# Tree.net
KiCad netlist of a schematic drawn in Altium Designer
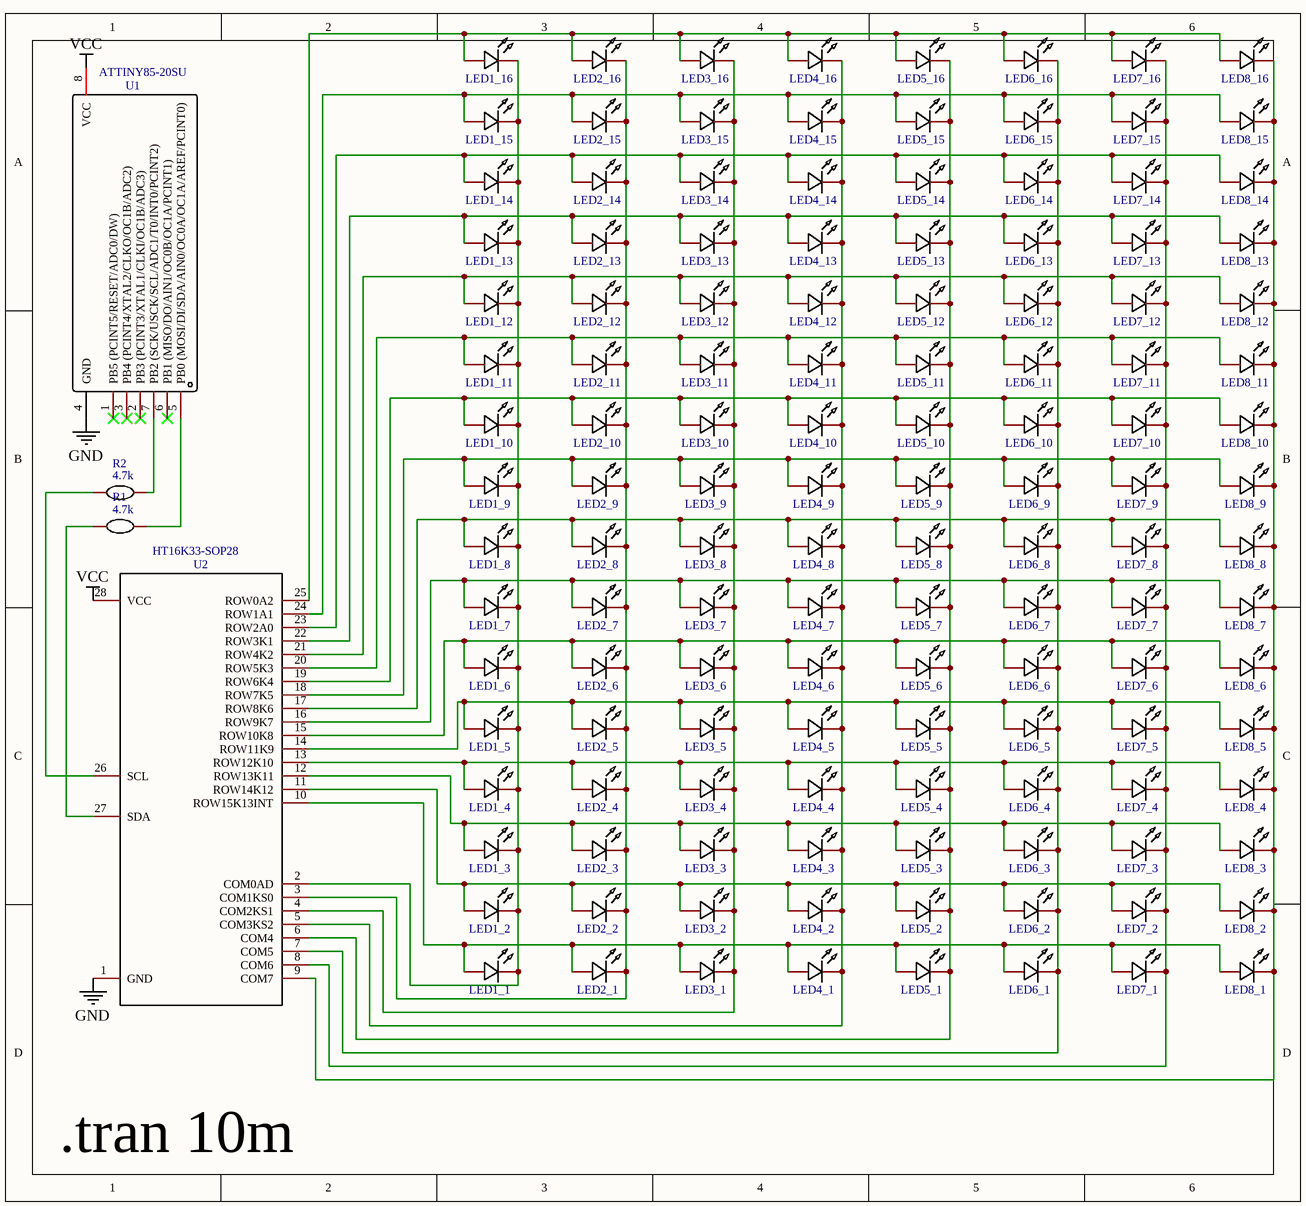
[diagram p0: Tree.schdoc]

(export (version "E")
  (design (tool "Eeschema 10.0.6"))
  (components
    (comp (ref "LED1_1")
      (value "19-217/GHC-YR1S2/3T")
      (fields (field (name "MANUFACTURER") "EVERLIGHT(台湾亿光)"))
      (libsource (lib "altium-import") (part "root_0_19-217/GHC-YR1S2/3T_"))
    )
    (comp (ref "LED1_2")
      (value "19-217/GHC-YR1S2/3T")
      (fields (field (name "MANUFACTURER") "EVERLIGHT(台湾亿光)"))
      (libsource (lib "altium-import") (part "root_0_19-217/GHC-YR1S2/3T_"))
    )
    (comp (ref "LED1_3")
      (value "19-217/GHC-YR1S2/3T")
      (fields (field (name "MANUFACTURER") "EVERLIGHT(台湾亿光)"))
      (libsource (lib "altium-import") (part "root_0_19-217/GHC-YR1S2/3T_"))
    )
    (comp (ref "LED1_4")
      (value "19-217/GHC-YR1S2/3T")
      (fields (field (name "MANUFACTURER") "EVERLIGHT(台湾亿光)"))
      (libsource (lib "altium-import") (part "root_0_19-217/GHC-YR1S2/3T_"))
    )
    (comp (ref "LED1_5")
      (value "19-217/GHC-YR1S2/3T")
      (fields (field (name "MANUFACTURER") "EVERLIGHT(台湾亿光)"))
      (libsource (lib "altium-import") (part "root_0_19-217/GHC-YR1S2/3T_"))
    )
    (comp (ref "LED1_6")
      (value "19-217/GHC-YR1S2/3T")
      (fields (field (name "MANUFACTURER") "EVERLIGHT(台湾亿光)"))
      (libsource (lib "altium-import") (part "root_0_19-217/GHC-YR1S2/3T_"))
    )
    (comp (ref "LED1_7")
      (value "19-217/GHC-YR1S2/3T")
      (fields (field (name "MANUFACTURER") "EVERLIGHT(台湾亿光)"))
      (libsource (lib "altium-import") (part "root_0_19-217/GHC-YR1S2/3T_"))
    )
    (comp (ref "LED1_8")
      (value "19-217/GHC-YR1S2/3T")
      (fields (field (name "MANUFACTURER") "EVERLIGHT(台湾亿光)"))
      (libsource (lib "altium-import") (part "root_0_19-217/GHC-YR1S2/3T_"))
    )
    (comp (ref "LED1_9")
      (value "19-217/GHC-YR1S2/3T")
      (fields (field (name "MANUFACTURER") "EVERLIGHT(台湾亿光)"))
      (libsource (lib "altium-import") (part "root_0_19-217/GHC-YR1S2/3T_"))
    )
    (comp (ref "LED1_10")
      (value "19-217/GHC-YR1S2/3T")
      (fields (field (name "MANUFACTURER") "EVERLIGHT(台湾亿光)"))
      (libsource (lib "altium-import") (part "root_0_19-217/GHC-YR1S2/3T_"))
    )
    (comp (ref "LED1_11")
      (value "19-217/BHC-ZL1M2RY/3T")
      (fields (field (name "MANUFACTURER") "EVERLIGHT(台湾亿光)"))
      (libsource (lib "altium-import") (part "root_0_19-217/BHC-ZL1M2RY/3T_"))
    )
    (comp (ref "LED1_12")
      (value "19-217/BHC-ZL1M2RY/3T")
      (fields (field (name "MANUFACTURER") "EVERLIGHT(台湾亿光)"))
      (libsource (lib "altium-import") (part "root_0_19-217/BHC-ZL1M2RY/3T_"))
    )
    (comp (ref "LED1_13")
      (value "19-217/BHC-ZL1M2RY/3T")
      (fields (field (name "MANUFACTURER") "EVERLIGHT(台湾亿光)"))
      (libsource (lib "altium-import") (part "root_0_19-217/BHC-ZL1M2RY/3T_"))
    )
    (comp (ref "LED1_14")
      (value "19-217/BHC-ZL1M2RY/3T")
      (fields (field (name "MANUFACTURER") "EVERLIGHT(台湾亿光)"))
      (libsource (lib "altium-import") (part "root_0_19-217/BHC-ZL1M2RY/3T_"))
    )
    (comp (ref "LED1_15")
      (value "19-217/BHC-ZL1M2RY/3T")
      (fields (field (name "MANUFACTURER") "EVERLIGHT(台湾亿光)"))
      (libsource (lib "altium-import") (part "root_0_19-217/BHC-ZL1M2RY/3T_"))
    )
    (comp (ref "LED1_16")
      (value "19-217/R6C-AL1M2VY/3T")
      (fields (field (name "MANUFACTURER") "EVERLIGHT(台湾亿光)"))
      (libsource (lib "altium-import") (part "root_0_19-217/R6C-AL1M2VY/3T_"))
    )
    (comp (ref "LED2_1")
      (value "19-217/GHC-YR1S2/3T")
      (fields (field (name "MANUFACTURER") "EVERLIGHT(台湾亿光)"))
      (libsource (lib "altium-import") (part "root_0_19-217/GHC-YR1S2/3T_"))
    )
    (comp (ref "LED2_2")
      (value "19-217/GHC-YR1S2/3T")
      (fields (field (name "MANUFACTURER") "EVERLIGHT(台湾亿光)"))
      (libsource (lib "altium-import") (part "root_0_19-217/GHC-YR1S2/3T_"))
    )
    (comp (ref "LED2_3")
      (value "19-217/GHC-YR1S2/3T")
      (fields (field (name "MANUFACTURER") "EVERLIGHT(台湾亿光)"))
      (libsource (lib "altium-import") (part "root_0_19-217/GHC-YR1S2/3T_"))
    )
    (comp (ref "LED2_4")
      (value "19-217/GHC-YR1S2/3T")
      (fields (field (name "MANUFACTURER") "EVERLIGHT(台湾亿光)"))
      (libsource (lib "altium-import") (part "root_0_19-217/GHC-YR1S2/3T_"))
    )
    (comp (ref "LED2_5")
      (value "19-217/GHC-YR1S2/3T")
      (fields (field (name "MANUFACTURER") "EVERLIGHT(台湾亿光)"))
      (libsource (lib "altium-import") (part "root_0_19-217/GHC-YR1S2/3T_"))
    )
    (comp (ref "LED2_6")
      (value "19-217/GHC-YR1S2/3T")
      (fields (field (name "MANUFACTURER") "EVERLIGHT(台湾亿光)"))
      (libsource (lib "altium-import") (part "root_0_19-217/GHC-YR1S2/3T_"))
    )
    (comp (ref "LED2_7")
      (value "19-217/GHC-YR1S2/3T")
      (fields (field (name "MANUFACTURER") "EVERLIGHT(台湾亿光)"))
      (libsource (lib "altium-import") (part "root_0_19-217/GHC-YR1S2/3T_"))
    )
    (comp (ref "LED2_8")
      (value "19-217/GHC-YR1S2/3T")
      (fields (field (name "MANUFACTURER") "EVERLIGHT(台湾亿光)"))
      (libsource (lib "altium-import") (part "root_0_19-217/GHC-YR1S2/3T_"))
    )
    (comp (ref "LED2_9")
      (value "19-217/GHC-YR1S2/3T")
      (fields (field (name "MANUFACTURER") "EVERLIGHT(台湾亿光)"))
      (libsource (lib "altium-import") (part "root_0_19-217/GHC-YR1S2/3T_"))
    )
    (comp (ref "LED2_10")
      (value "19-217/GHC-YR1S2/3T")
      (fields (field (name "MANUFACTURER") "EVERLIGHT(台湾亿光)"))
      (libsource (lib "altium-import") (part "root_0_19-217/GHC-YR1S2/3T_"))
    )
    (comp (ref "LED2_11")
      (value "19-217/BHC-ZL1M2RY/3T")
      (fields (field (name "MANUFACTURER") "EVERLIGHT(台湾亿光)"))
      (libsource (lib "altium-import") (part "root_0_19-217/BHC-ZL1M2RY/3T_"))
    )
    (comp (ref "LED2_12")
      (value "19-217/BHC-ZL1M2RY/3T")
      (fields (field (name "MANUFACTURER") "EVERLIGHT(台湾亿光)"))
      (libsource (lib "altium-import") (part "root_0_19-217/BHC-ZL1M2RY/3T_"))
    )
    (comp (ref "LED2_13")
      (value "19-217/BHC-ZL1M2RY/3T")
      (fields (field (name "MANUFACTURER") "EVERLIGHT(台湾亿光)"))
      (libsource (lib "altium-import") (part "root_0_19-217/BHC-ZL1M2RY/3T_"))
    )
    (comp (ref "LED2_14")
      (value "19-217/BHC-ZL1M2RY/3T")
      (fields (field (name "MANUFACTURER") "EVERLIGHT(台湾亿光)"))
      (libsource (lib "altium-import") (part "root_0_19-217/BHC-ZL1M2RY/3T_"))
    )
    (comp (ref "LED2_15")
      (value "19-217/BHC-ZL1M2RY/3T")
      (fields (field (name "MANUFACTURER") "EVERLIGHT(台湾亿光)"))
      (libsource (lib "altium-import") (part "root_0_19-217/BHC-ZL1M2RY/3T_"))
    )
    (comp (ref "LED2_16")
      (value "19-217/R6C-AL1M2VY/3T")
      (fields (field (name "MANUFACTURER") "EVERLIGHT(台湾亿光)"))
      (libsource (lib "altium-import") (part "root_0_19-217/R6C-AL1M2VY/3T_"))
    )
    (comp (ref "LED3_1")
      (value "19-217/GHC-YR1S2/3T")
      (fields (field (name "MANUFACTURER") "EVERLIGHT(台湾亿光)"))
      (libsource (lib "altium-import") (part "root_0_19-217/GHC-YR1S2/3T_"))
    )
    (comp (ref "LED3_2")
      (value "19-217/GHC-YR1S2/3T")
      (fields (field (name "MANUFACTURER") "EVERLIGHT(台湾亿光)"))
      (libsource (lib "altium-import") (part "root_0_19-217/GHC-YR1S2/3T_"))
    )
    (comp (ref "LED3_3")
      (value "19-217/GHC-YR1S2/3T")
      (fields (field (name "MANUFACTURER") "EVERLIGHT(台湾亿光)"))
      (libsource (lib "altium-import") (part "root_0_19-217/GHC-YR1S2/3T_"))
    )
    (comp (ref "LED3_4")
      (value "19-217/GHC-YR1S2/3T")
      (fields (field (name "MANUFACTURER") "EVERLIGHT(台湾亿光)"))
      (libsource (lib "altium-import") (part "root_0_19-217/GHC-YR1S2/3T_"))
    )
    (comp (ref "LED3_5")
      (value "19-217/GHC-YR1S2/3T")
      (fields (field (name "MANUFACTURER") "EVERLIGHT(台湾亿光)"))
      (libsource (lib "altium-import") (part "root_0_19-217/GHC-YR1S2/3T_"))
    )
    (comp (ref "LED3_6")
      (value "19-217/GHC-YR1S2/3T")
      (fields (field (name "MANUFACTURER") "EVERLIGHT(台湾亿光)"))
      (libsource (lib "altium-import") (part "root_0_19-217/GHC-YR1S2/3T_"))
    )
    (comp (ref "LED3_7")
      (value "19-217/GHC-YR1S2/3T")
      (fields (field (name "MANUFACTURER") "EVERLIGHT(台湾亿光)"))
      (libsource (lib "altium-import") (part "root_0_19-217/GHC-YR1S2/3T_"))
    )
    (comp (ref "LED3_8")
      (value "19-217/GHC-YR1S2/3T")
      (fields (field (name "MANUFACTURER") "EVERLIGHT(台湾亿光)"))
      (libsource (lib "altium-import") (part "root_0_19-217/GHC-YR1S2/3T_"))
    )
    (comp (ref "LED3_9")
      (value "19-217/GHC-YR1S2/3T")
      (fields (field (name "MANUFACTURER") "EVERLIGHT(台湾亿光)"))
      (libsource (lib "altium-import") (part "root_0_19-217/GHC-YR1S2/3T_"))
    )
    (comp (ref "LED3_10")
      (value "19-217/GHC-YR1S2/3T")
      (fields (field (name "MANUFACTURER") "EVERLIGHT(台湾亿光)"))
      (libsource (lib "altium-import") (part "root_0_19-217/GHC-YR1S2/3T_"))
    )
    (comp (ref "LED3_11")
      (value "19-217/BHC-ZL1M2RY/3T")
      (fields (field (name "MANUFACTURER") "EVERLIGHT(台湾亿光)"))
      (libsource (lib "altium-import") (part "root_0_19-217/BHC-ZL1M2RY/3T_"))
    )
    (comp (ref "LED3_12")
      (value "19-217/BHC-ZL1M2RY/3T")
      (fields (field (name "MANUFACTURER") "EVERLIGHT(台湾亿光)"))
      (libsource (lib "altium-import") (part "root_0_19-217/BHC-ZL1M2RY/3T_"))
    )
    (comp (ref "LED3_13")
      (value "19-217/BHC-ZL1M2RY/3T")
      (fields (field (name "MANUFACTURER") "EVERLIGHT(台湾亿光)"))
      (libsource (lib "altium-import") (part "root_0_19-217/BHC-ZL1M2RY/3T_"))
    )
    (comp (ref "LED3_14")
      (value "19-217/BHC-ZL1M2RY/3T")
      (fields (field (name "MANUFACTURER") "EVERLIGHT(台湾亿光)"))
      (libsource (lib "altium-import") (part "root_0_19-217/BHC-ZL1M2RY/3T_"))
    )
    (comp (ref "LED3_15")
      (value "19-217/BHC-ZL1M2RY/3T")
      (fields (field (name "MANUFACTURER") "EVERLIGHT(台湾亿光)"))
      (libsource (lib "altium-import") (part "root_0_19-217/BHC-ZL1M2RY/3T_"))
    )
    (comp (ref "LED3_16")
      (value "19-217/R6C-AL1M2VY/3T")
      (fields (field (name "MANUFACTURER") "EVERLIGHT(台湾亿光)"))
      (libsource (lib "altium-import") (part "root_0_19-217/R6C-AL1M2VY/3T_"))
    )
    (comp (ref "LED4_1")
      (value "19-217/GHC-YR1S2/3T")
      (fields (field (name "MANUFACTURER") "EVERLIGHT(台湾亿光)"))
      (libsource (lib "altium-import") (part "root_0_19-217/GHC-YR1S2/3T_"))
    )
    (comp (ref "LED4_2")
      (value "19-217/GHC-YR1S2/3T")
      (fields (field (name "MANUFACTURER") "EVERLIGHT(台湾亿光)"))
      (libsource (lib "altium-import") (part "root_0_19-217/GHC-YR1S2/3T_"))
    )
    (comp (ref "LED4_3")
      (value "19-217/GHC-YR1S2/3T")
      (fields (field (name "MANUFACTURER") "EVERLIGHT(台湾亿光)"))
      (libsource (lib "altium-import") (part "root_0_19-217/GHC-YR1S2/3T_"))
    )
    (comp (ref "LED4_4")
      (value "19-217/GHC-YR1S2/3T")
      (fields (field (name "MANUFACTURER") "EVERLIGHT(台湾亿光)"))
      (libsource (lib "altium-import") (part "root_0_19-217/GHC-YR1S2/3T_"))
    )
    (comp (ref "LED4_5")
      (value "19-217/GHC-YR1S2/3T")
      (fields (field (name "MANUFACTURER") "EVERLIGHT(台湾亿光)"))
      (libsource (lib "altium-import") (part "root_0_19-217/GHC-YR1S2/3T_"))
    )
    (comp (ref "LED4_6")
      (value "19-217/GHC-YR1S2/3T")
      (fields (field (name "MANUFACTURER") "EVERLIGHT(台湾亿光)"))
      (libsource (lib "altium-import") (part "root_0_19-217/GHC-YR1S2/3T_"))
    )
    (comp (ref "LED4_7")
      (value "19-217/GHC-YR1S2/3T")
      (fields (field (name "MANUFACTURER") "EVERLIGHT(台湾亿光)"))
      (libsource (lib "altium-import") (part "root_0_19-217/GHC-YR1S2/3T_"))
    )
    (comp (ref "LED4_8")
      (value "19-217/GHC-YR1S2/3T")
      (fields (field (name "MANUFACTURER") "EVERLIGHT(台湾亿光)"))
      (libsource (lib "altium-import") (part "root_0_19-217/GHC-YR1S2/3T_"))
    )
    (comp (ref "LED4_9")
      (value "19-217/GHC-YR1S2/3T")
      (fields (field (name "MANUFACTURER") "EVERLIGHT(台湾亿光)"))
      (libsource (lib "altium-import") (part "root_0_19-217/GHC-YR1S2/3T_"))
    )
    (comp (ref "LED4_10")
      (value "19-217/GHC-YR1S2/3T")
      (fields (field (name "MANUFACTURER") "EVERLIGHT(台湾亿光)"))
      (libsource (lib "altium-import") (part "root_0_19-217/GHC-YR1S2/3T_"))
    )
    (comp (ref "LED4_11")
      (value "19-217/BHC-ZL1M2RY/3T")
      (fields (field (name "MANUFACTURER") "EVERLIGHT(台湾亿光)"))
      (libsource (lib "altium-import") (part "root_0_19-217/BHC-ZL1M2RY/3T_"))
    )
    (comp (ref "LED4_12")
      (value "19-217/BHC-ZL1M2RY/3T")
      (fields (field (name "MANUFACTURER") "EVERLIGHT(台湾亿光)"))
      (libsource (lib "altium-import") (part "root_0_19-217/BHC-ZL1M2RY/3T_"))
    )
    (comp (ref "LED4_13")
      (value "19-217/BHC-ZL1M2RY/3T")
      (fields (field (name "MANUFACTURER") "EVERLIGHT(台湾亿光)"))
      (libsource (lib "altium-import") (part "root_0_19-217/BHC-ZL1M2RY/3T_"))
    )
    (comp (ref "LED4_14")
      (value "19-217/BHC-ZL1M2RY/3T")
      (fields (field (name "MANUFACTURER") "EVERLIGHT(台湾亿光)"))
      (libsource (lib "altium-import") (part "root_0_19-217/BHC-ZL1M2RY/3T_"))
    )
    (comp (ref "LED4_15")
      (value "19-217/BHC-ZL1M2RY/3T")
      (fields (field (name "MANUFACTURER") "EVERLIGHT(台湾亿光)"))
      (libsource (lib "altium-import") (part "root_0_19-217/BHC-ZL1M2RY/3T_"))
    )
    (comp (ref "LED4_16")
      (value "19-217/R6C-AL1M2VY/3T")
      (fields (field (name "MANUFACTURER") "EVERLIGHT(台湾亿光)"))
      (libsource (lib "altium-import") (part "root_0_19-217/R6C-AL1M2VY/3T_"))
    )
    (comp (ref "LED5_1")
      (value "19-217/GHC-YR1S2/3T")
      (fields (field (name "MANUFACTURER") "EVERLIGHT(台湾亿光)"))
      (libsource (lib "altium-import") (part "root_0_19-217/GHC-YR1S2/3T_"))
    )
    (comp (ref "LED5_2")
      (value "19-217/GHC-YR1S2/3T")
      (fields (field (name "MANUFACTURER") "EVERLIGHT(台湾亿光)"))
      (libsource (lib "altium-import") (part "root_0_19-217/GHC-YR1S2/3T_"))
    )
    (comp (ref "LED5_3")
      (value "19-217/GHC-YR1S2/3T")
      (fields (field (name "MANUFACTURER") "EVERLIGHT(台湾亿光)"))
      (libsource (lib "altium-import") (part "root_0_19-217/GHC-YR1S2/3T_"))
    )
    (comp (ref "LED5_4")
      (value "19-217/GHC-YR1S2/3T")
      (fields (field (name "MANUFACTURER") "EVERLIGHT(台湾亿光)"))
      (libsource (lib "altium-import") (part "root_0_19-217/GHC-YR1S2/3T_"))
    )
    (comp (ref "LED5_5")
      (value "19-217/GHC-YR1S2/3T")
      (fields (field (name "MANUFACTURER") "EVERLIGHT(台湾亿光)"))
      (libsource (lib "altium-import") (part "root_0_19-217/GHC-YR1S2/3T_"))
    )
    (comp (ref "LED5_6")
      (value "19-217/GHC-YR1S2/3T")
      (fields (field (name "MANUFACTURER") "EVERLIGHT(台湾亿光)"))
      (libsource (lib "altium-import") (part "root_0_19-217/GHC-YR1S2/3T_"))
    )
    (comp (ref "LED5_7")
      (value "19-217/GHC-YR1S2/3T")
      (fields (field (name "MANUFACTURER") "EVERLIGHT(台湾亿光)"))
      (libsource (lib "altium-import") (part "root_0_19-217/GHC-YR1S2/3T_"))
    )
    (comp (ref "LED5_8")
      (value "19-217/GHC-YR1S2/3T")
      (fields (field (name "MANUFACTURER") "EVERLIGHT(台湾亿光)"))
      (libsource (lib "altium-import") (part "root_0_19-217/GHC-YR1S2/3T_"))
    )
    (comp (ref "LED5_9")
      (value "19-217/GHC-YR1S2/3T")
      (fields (field (name "MANUFACTURER") "EVERLIGHT(台湾亿光)"))
      (libsource (lib "altium-import") (part "root_0_19-217/GHC-YR1S2/3T_"))
    )
    (comp (ref "LED5_10")
      (value "19-217/GHC-YR1S2/3T")
      (fields (field (name "MANUFACTURER") "EVERLIGHT(台湾亿光)"))
      (libsource (lib "altium-import") (part "root_0_19-217/GHC-YR1S2/3T_"))
    )
    (comp (ref "LED5_11")
      (value "19-217/BHC-ZL1M2RY/3T")
      (fields (field (name "MANUFACTURER") "EVERLIGHT(台湾亿光)"))
      (libsource (lib "altium-import") (part "root_0_19-217/BHC-ZL1M2RY/3T_"))
    )
    (comp (ref "LED5_12")
      (value "19-217/BHC-ZL1M2RY/3T")
      (fields (field (name "MANUFACTURER") "EVERLIGHT(台湾亿光)"))
      (libsource (lib "altium-import") (part "root_0_19-217/BHC-ZL1M2RY/3T_"))
    )
    (comp (ref "LED5_13")
      (value "19-217/BHC-ZL1M2RY/3T")
      (fields (field (name "MANUFACTURER") "EVERLIGHT(台湾亿光)"))
      (libsource (lib "altium-import") (part "root_0_19-217/BHC-ZL1M2RY/3T_"))
    )
    (comp (ref "LED5_14")
      (value "19-217/BHC-ZL1M2RY/3T")
      (fields (field (name "MANUFACTURER") "EVERLIGHT(台湾亿光)"))
      (libsource (lib "altium-import") (part "root_0_19-217/BHC-ZL1M2RY/3T_"))
    )
    (comp (ref "LED5_15")
      (value "19-217/BHC-ZL1M2RY/3T")
      (fields (field (name "MANUFACTURER") "EVERLIGHT(台湾亿光)"))
      (libsource (lib "altium-import") (part "root_0_19-217/BHC-ZL1M2RY/3T_"))
    )
    (comp (ref "LED5_16")
      (value "19-217/R6C-AL1M2VY/3T")
      (fields (field (name "MANUFACTURER") "EVERLIGHT(台湾亿光)"))
      (libsource (lib "altium-import") (part "root_0_19-217/R6C-AL1M2VY/3T_"))
    )
    (comp (ref "LED6_1")
      (value "19-217/GHC-YR1S2/3T")
      (fields (field (name "MANUFACTURER") "EVERLIGHT(台湾亿光)"))
      (libsource (lib "altium-import") (part "root_0_19-217/GHC-YR1S2/3T_"))
    )
    (comp (ref "LED6_2")
      (value "19-217/GHC-YR1S2/3T")
      (fields (field (name "MANUFACTURER") "EVERLIGHT(台湾亿光)"))
      (libsource (lib "altium-import") (part "root_0_19-217/GHC-YR1S2/3T_"))
    )
    (comp (ref "LED6_3")
      (value "19-217/GHC-YR1S2/3T")
      (fields (field (name "MANUFACTURER") "EVERLIGHT(台湾亿光)"))
      (libsource (lib "altium-import") (part "root_0_19-217/GHC-YR1S2/3T_"))
    )
    (comp (ref "LED6_4")
      (value "19-217/GHC-YR1S2/3T")
      (fields (field (name "MANUFACTURER") "EVERLIGHT(台湾亿光)"))
      (libsource (lib "altium-import") (part "root_0_19-217/GHC-YR1S2/3T_"))
    )
    (comp (ref "LED6_5")
      (value "19-217/GHC-YR1S2/3T")
      (fields (field (name "MANUFACTURER") "EVERLIGHT(台湾亿光)"))
      (libsource (lib "altium-import") (part "root_0_19-217/GHC-YR1S2/3T_"))
    )
    (comp (ref "LED6_6")
      (value "19-217/GHC-YR1S2/3T")
      (fields (field (name "MANUFACTURER") "EVERLIGHT(台湾亿光)"))
      (libsource (lib "altium-import") (part "root_0_19-217/GHC-YR1S2/3T_"))
    )
    (comp (ref "LED6_7")
      (value "19-217/GHC-YR1S2/3T")
      (fields (field (name "MANUFACTURER") "EVERLIGHT(台湾亿光)"))
      (libsource (lib "altium-import") (part "root_0_19-217/GHC-YR1S2/3T_"))
    )
    (comp (ref "LED6_8")
      (value "19-217/GHC-YR1S2/3T")
      (fields (field (name "MANUFACTURER") "EVERLIGHT(台湾亿光)"))
      (libsource (lib "altium-import") (part "root_0_19-217/GHC-YR1S2/3T_"))
    )
    (comp (ref "LED6_9")
      (value "19-217/GHC-YR1S2/3T")
      (fields (field (name "MANUFACTURER") "EVERLIGHT(台湾亿光)"))
      (libsource (lib "altium-import") (part "root_0_19-217/GHC-YR1S2/3T_"))
    )
    (comp (ref "LED6_10")
      (value "19-217/GHC-YR1S2/3T")
      (fields (field (name "MANUFACTURER") "EVERLIGHT(台湾亿光)"))
      (libsource (lib "altium-import") (part "root_0_19-217/GHC-YR1S2/3T_"))
    )
    (comp (ref "LED6_11")
      (value "19-217/BHC-ZL1M2RY/3T")
      (fields (field (name "MANUFACTURER") "EVERLIGHT(台湾亿光)"))
      (libsource (lib "altium-import") (part "root_0_19-217/BHC-ZL1M2RY/3T_"))
    )
    (comp (ref "LED6_12")
      (value "19-217/BHC-ZL1M2RY/3T")
      (fields (field (name "MANUFACTURER") "EVERLIGHT(台湾亿光)"))
      (libsource (lib "altium-import") (part "root_0_19-217/BHC-ZL1M2RY/3T_"))
    )
    (comp (ref "LED6_13")
      (value "19-217/BHC-ZL1M2RY/3T")
      (fields (field (name "MANUFACTURER") "EVERLIGHT(台湾亿光)"))
      (libsource (lib "altium-import") (part "root_0_19-217/BHC-ZL1M2RY/3T_"))
    )
    (comp (ref "LED6_14")
      (value "19-217/BHC-ZL1M2RY/3T")
      (fields (field (name "MANUFACTURER") "EVERLIGHT(台湾亿光)"))
      (libsource (lib "altium-import") (part "root_0_19-217/BHC-ZL1M2RY/3T_"))
    )
    (comp (ref "LED6_15")
      (value "19-217/BHC-ZL1M2RY/3T")
      (fields (field (name "MANUFACTURER") "EVERLIGHT(台湾亿光)"))
      (libsource (lib "altium-import") (part "root_0_19-217/BHC-ZL1M2RY/3T_"))
    )
    (comp (ref "LED6_16")
      (value "19-217/R6C-AL1M2VY/3T")
      (fields (field (name "MANUFACTURER") "EVERLIGHT(台湾亿光)"))
      (libsource (lib "altium-import") (part "root_0_19-217/R6C-AL1M2VY/3T_"))
    )
    (comp (ref "LED7_1")
      (value "19-217/GHC-YR1S2/3T")
      (fields (field (name "MANUFACTURER") "EVERLIGHT(台湾亿光)"))
      (libsource (lib "altium-import") (part "root_0_19-217/GHC-YR1S2/3T_"))
    )
    (comp (ref "LED7_2")
      (value "19-217/GHC-YR1S2/3T")
      (fields (field (name "MANUFACTURER") "EVERLIGHT(台湾亿光)"))
      (libsource (lib "altium-import") (part "root_0_19-217/GHC-YR1S2/3T_"))
    )
    (comp (ref "LED7_3")
      (value "19-217/GHC-YR1S2/3T")
      (fields (field (name "MANUFACTURER") "EVERLIGHT(台湾亿光)"))
      (libsource (lib "altium-import") (part "root_0_19-217/GHC-YR1S2/3T_"))
    )
    (comp (ref "LED7_4")
      (value "19-217/GHC-YR1S2/3T")
      (fields (field (name "MANUFACTURER") "EVERLIGHT(台湾亿光)"))
      (libsource (lib "altium-import") (part "root_0_19-217/GHC-YR1S2/3T_"))
    )
    (comp (ref "LED7_5")
      (value "19-217/GHC-YR1S2/3T")
      (fields (field (name "MANUFACTURER") "EVERLIGHT(台湾亿光)"))
      (libsource (lib "altium-import") (part "root_0_19-217/GHC-YR1S2/3T_"))
    )
    (comp (ref "LED7_6")
      (value "19-217/GHC-YR1S2/3T")
      (fields (field (name "MANUFACTURER") "EVERLIGHT(台湾亿光)"))
      (libsource (lib "altium-import") (part "root_0_19-217/GHC-YR1S2/3T_"))
    )
    (comp (ref "LED7_7")
      (value "19-217/GHC-YR1S2/3T")
      (fields (field (name "MANUFACTURER") "EVERLIGHT(台湾亿光)"))
      (libsource (lib "altium-import") (part "root_0_19-217/GHC-YR1S2/3T_"))
    )
    (comp (ref "LED7_8")
      (value "19-217/GHC-YR1S2/3T")
      (fields (field (name "MANUFACTURER") "EVERLIGHT(台湾亿光)"))
      (libsource (lib "altium-import") (part "root_0_19-217/GHC-YR1S2/3T_"))
    )
    (comp (ref "LED7_9")
      (value "19-217/GHC-YR1S2/3T")
      (fields (field (name "MANUFACTURER") "EVERLIGHT(台湾亿光)"))
      (libsource (lib "altium-import") (part "root_0_19-217/GHC-YR1S2/3T_"))
    )
    (comp (ref "LED7_10")
      (value "19-217/GHC-YR1S2/3T")
      (fields (field (name "MANUFACTURER") "EVERLIGHT(台湾亿光)"))
      (libsource (lib "altium-import") (part "root_0_19-217/GHC-YR1S2/3T_"))
    )
    (comp (ref "LED7_11")
      (value "19-217/BHC-ZL1M2RY/3T")
      (fields (field (name "MANUFACTURER") "EVERLIGHT(台湾亿光)"))
      (libsource (lib "altium-import") (part "root_0_19-217/BHC-ZL1M2RY/3T_"))
    )
    (comp (ref "LED7_12")
      (value "19-217/BHC-ZL1M2RY/3T")
      (fields (field (name "MANUFACTURER") "EVERLIGHT(台湾亿光)"))
      (libsource (lib "altium-import") (part "root_0_19-217/BHC-ZL1M2RY/3T_"))
    )
    (comp (ref "LED7_13")
      (value "19-217/BHC-ZL1M2RY/3T")
      (fields (field (name "MANUFACTURER") "EVERLIGHT(台湾亿光)"))
      (libsource (lib "altium-import") (part "root_0_19-217/BHC-ZL1M2RY/3T_"))
    )
    (comp (ref "LED7_14")
      (value "19-217/BHC-ZL1M2RY/3T")
      (fields (field (name "MANUFACTURER") "EVERLIGHT(台湾亿光)"))
      (libsource (lib "altium-import") (part "root_0_19-217/BHC-ZL1M2RY/3T_"))
    )
    (comp (ref "LED7_15")
      (value "19-217/BHC-ZL1M2RY/3T")
      (fields (field (name "MANUFACTURER") "EVERLIGHT(台湾亿光)"))
      (libsource (lib "altium-import") (part "root_0_19-217/BHC-ZL1M2RY/3T_"))
    )
    (comp (ref "LED7_16")
      (value "19-217/R6C-AL1M2VY/3T")
      (fields (field (name "MANUFACTURER") "EVERLIGHT(台湾亿光)"))
      (libsource (lib "altium-import") (part "root_0_19-217/R6C-AL1M2VY/3T_"))
    )
    (comp (ref "LED8_1")
      (value "19-217/GHC-YR1S2/3T")
      (fields (field (name "MANUFACTURER") "EVERLIGHT(台湾亿光)"))
      (libsource (lib "altium-import") (part "root_0_19-217/GHC-YR1S2/3T_"))
    )
    (comp (ref "LED8_2")
      (value "19-217/GHC-YR1S2/3T")
      (fields (field (name "MANUFACTURER") "EVERLIGHT(台湾亿光)"))
      (libsource (lib "altium-import") (part "root_0_19-217/GHC-YR1S2/3T_"))
    )
    (comp (ref "LED8_3")
      (value "19-217/GHC-YR1S2/3T")
      (fields (field (name "MANUFACTURER") "EVERLIGHT(台湾亿光)"))
      (libsource (lib "altium-import") (part "root_0_19-217/GHC-YR1S2/3T_"))
    )
    (comp (ref "LED8_4")
      (value "19-217/GHC-YR1S2/3T")
      (fields (field (name "MANUFACTURER") "EVERLIGHT(台湾亿光)"))
      (libsource (lib "altium-import") (part "root_0_19-217/GHC-YR1S2/3T_"))
    )
    (comp (ref "LED8_5")
      (value "19-217/GHC-YR1S2/3T")
      (fields (field (name "MANUFACTURER") "EVERLIGHT(台湾亿光)"))
      (libsource (lib "altium-import") (part "root_0_19-217/GHC-YR1S2/3T_"))
    )
    (comp (ref "LED8_6")
      (value "19-217/GHC-YR1S2/3T")
      (fields (field (name "MANUFACTURER") "EVERLIGHT(台湾亿光)"))
      (libsource (lib "altium-import") (part "root_0_19-217/GHC-YR1S2/3T_"))
    )
    (comp (ref "LED8_7")
      (value "19-217/GHC-YR1S2/3T")
      (fields (field (name "MANUFACTURER") "EVERLIGHT(台湾亿光)"))
      (libsource (lib "altium-import") (part "root_0_19-217/GHC-YR1S2/3T_"))
    )
    (comp (ref "LED8_8")
      (value "19-217/GHC-YR1S2/3T")
      (fields (field (name "MANUFACTURER") "EVERLIGHT(台湾亿光)"))
      (libsource (lib "altium-import") (part "root_0_19-217/GHC-YR1S2/3T_"))
    )
    (comp (ref "LED8_9")
      (value "19-217/GHC-YR1S2/3T")
      (fields (field (name "MANUFACTURER") "EVERLIGHT(台湾亿光)"))
      (libsource (lib "altium-import") (part "root_0_19-217/GHC-YR1S2/3T_"))
    )
    (comp (ref "LED8_10")
      (value "19-217/GHC-YR1S2/3T")
      (fields (field (name "MANUFACTURER") "EVERLIGHT(台湾亿光)"))
      (libsource (lib "altium-import") (part "root_0_19-217/GHC-YR1S2/3T_"))
    )
    (comp (ref "LED8_11")
      (value "19-217/BHC-ZL1M2RY/3T")
      (fields (field (name "MANUFACTURER") "EVERLIGHT(台湾亿光)"))
      (libsource (lib "altium-import") (part "root_0_19-217/BHC-ZL1M2RY/3T_"))
    )
    (comp (ref "LED8_12")
      (value "19-217/BHC-ZL1M2RY/3T")
      (fields (field (name "MANUFACTURER") "EVERLIGHT(台湾亿光)"))
      (libsource (lib "altium-import") (part "root_0_19-217/BHC-ZL1M2RY/3T_"))
    )
    (comp (ref "LED8_13")
      (value "19-217/BHC-ZL1M2RY/3T")
      (fields (field (name "MANUFACTURER") "EVERLIGHT(台湾亿光)"))
      (libsource (lib "altium-import") (part "root_0_19-217/BHC-ZL1M2RY/3T_"))
    )
    (comp (ref "LED8_14")
      (value "19-217/BHC-ZL1M2RY/3T")
      (fields (field (name "MANUFACTURER") "EVERLIGHT(台湾亿光)"))
      (libsource (lib "altium-import") (part "root_0_19-217/BHC-ZL1M2RY/3T_"))
    )
    (comp (ref "LED8_15")
      (value "19-217/BHC-ZL1M2RY/3T")
      (fields (field (name "MANUFACTURER") "EVERLIGHT(台湾亿光)"))
      (libsource (lib "altium-import") (part "root_0_19-217/BHC-ZL1M2RY/3T_"))
    )
    (comp (ref "LED8_16")
      (value "19-217/R6C-AL1M2VY/3T")
      (fields (field (name "MANUFACTURER") "EVERLIGHT(台湾亿光)"))
      (libsource (lib "altium-import") (part "root_0_19-217/R6C-AL1M2VY/3T_"))
    )
    (comp (ref "R1")
      (value "4.7k")
      (fields (field (name "NAME") "4.7k"))
      (libsource (lib "altium-import") (part "root_0_4.7k_"))
    )
    (comp (ref "R2")
      (value "4.7k")
      (fields (field (name "NAME") "4.7k"))
      (libsource (lib "altium-import") (part "root_0_4.7k_"))
    )
    (comp (ref "U1")
      (value "ATTINY85-20SU")
      (fields (field (name "NAME") "ATTINY85-20SU") (field (name "MANUFACTURER") "MICROCHIP"))
      (libsource (lib "altium-import") (part "root_3_ATTINY85-20SU_"))
    )
    (comp (ref "U2")
      (value "HT16K33-SOP28")
      (fields (field (name "NAME") "HT16K33-SOP28"))
      (libsource (lib "altium-import") (part "root_0_HT16K33-SOP28_"))
    )
  )
  (nets
    (net (code "1") (name "GND") (class "Default")
      (node (ref "U1") (pin "4") (pinfunction "GND_4") (pintype "passive"))
      (node (ref "U2") (pin "1") (pinfunction "GND_1") (pintype "passive"))
    )
    (net (code "2") (name "Net-(U1-PB0_(MOSI{slash}DI{slash}SDA{slash}AIN0{slash}OC0A{slash}OC1A{slash}AREF{slash}PCINT0))") (class "Default")
      (node (ref "R1") (pin "2") (pinfunction "2_2") (pintype "passive"))
      (node (ref "U1") (pin "5") (pinfunction "PB0_(MOSI/DI/SDA/AIN0/OC0A/OC1A/AREF/PCINT0)_5") (pintype "passive"))
    )
    (net (code "3") (name "Net-(U1-PB2_(SCK{slash}USCK{slash}SCL{slash}ADC1{slash}T0{slash}INT0{slash}PCINT2))") (class "Default")
      (node (ref "R2") (pin "2") (pinfunction "2_2") (pintype "passive"))
      (node (ref "U1") (pin "7") (pinfunction "PB2_(SCK/USCK/SCL/ADC1/T0/INT0/PCINT2)_7") (pintype "passive"))
    )
    (net (code "4") (name "Net-(U2-COM0AD)") (class "Default")
      (node (ref "LED1_1") (pin "2") (pinfunction "2_2") (pintype "passive"))
      (node (ref "LED1_10") (pin "2") (pinfunction "2_2") (pintype "passive"))
      (node (ref "LED1_11") (pin "2") (pinfunction "2_2") (pintype "passive"))
      (node (ref "LED1_12") (pin "2") (pinfunction "2_2") (pintype "passive"))
      (node (ref "LED1_13") (pin "2") (pinfunction "2_2") (pintype "passive"))
      (node (ref "LED1_14") (pin "2") (pinfunction "2_2") (pintype "passive"))
      (node (ref "LED1_15") (pin "2") (pinfunction "2_2") (pintype "passive"))
      (node (ref "LED1_16") (pin "2") (pinfunction "2_2") (pintype "passive"))
      (node (ref "LED1_2") (pin "2") (pinfunction "2_2") (pintype "passive"))
      (node (ref "LED1_3") (pin "2") (pinfunction "2_2") (pintype "passive"))
      (node (ref "LED1_4") (pin "2") (pinfunction "2_2") (pintype "passive"))
      (node (ref "LED1_5") (pin "2") (pinfunction "2_2") (pintype "passive"))
      (node (ref "LED1_6") (pin "2") (pinfunction "2_2") (pintype "passive"))
      (node (ref "LED1_7") (pin "2") (pinfunction "2_2") (pintype "passive"))
      (node (ref "LED1_8") (pin "2") (pinfunction "2_2") (pintype "passive"))
      (node (ref "LED1_9") (pin "2") (pinfunction "2_2") (pintype "passive"))
      (node (ref "U2") (pin "2") (pinfunction "COM0AD_2") (pintype "passive"))
    )
    (net (code "5") (name "Net-(U2-COM1KS0)") (class "Default")
      (node (ref "LED2_1") (pin "2") (pinfunction "2_2") (pintype "passive"))
      (node (ref "LED2_10") (pin "2") (pinfunction "2_2") (pintype "passive"))
      (node (ref "LED2_11") (pin "2") (pinfunction "2_2") (pintype "passive"))
      (node (ref "LED2_12") (pin "2") (pinfunction "2_2") (pintype "passive"))
      (node (ref "LED2_13") (pin "2") (pinfunction "2_2") (pintype "passive"))
      (node (ref "LED2_14") (pin "2") (pinfunction "2_2") (pintype "passive"))
      (node (ref "LED2_15") (pin "2") (pinfunction "2_2") (pintype "passive"))
      (node (ref "LED2_16") (pin "2") (pinfunction "2_2") (pintype "passive"))
      (node (ref "LED2_2") (pin "2") (pinfunction "2_2") (pintype "passive"))
      (node (ref "LED2_3") (pin "2") (pinfunction "2_2") (pintype "passive"))
      (node (ref "LED2_4") (pin "2") (pinfunction "2_2") (pintype "passive"))
      (node (ref "LED2_5") (pin "2") (pinfunction "2_2") (pintype "passive"))
      (node (ref "LED2_6") (pin "2") (pinfunction "2_2") (pintype "passive"))
      (node (ref "LED2_7") (pin "2") (pinfunction "2_2") (pintype "passive"))
      (node (ref "LED2_8") (pin "2") (pinfunction "2_2") (pintype "passive"))
      (node (ref "LED2_9") (pin "2") (pinfunction "2_2") (pintype "passive"))
      (node (ref "U2") (pin "3") (pinfunction "COM1KS0_3") (pintype "passive"))
    )
    (net (code "6") (name "Net-(U2-COM2KS1)") (class "Default")
      (node (ref "LED3_1") (pin "2") (pinfunction "2_2") (pintype "passive"))
      (node (ref "LED3_10") (pin "2") (pinfunction "2_2") (pintype "passive"))
      (node (ref "LED3_11") (pin "2") (pinfunction "2_2") (pintype "passive"))
      (node (ref "LED3_12") (pin "2") (pinfunction "2_2") (pintype "passive"))
      (node (ref "LED3_13") (pin "2") (pinfunction "2_2") (pintype "passive"))
      (node (ref "LED3_14") (pin "2") (pinfunction "2_2") (pintype "passive"))
      (node (ref "LED3_15") (pin "2") (pinfunction "2_2") (pintype "passive"))
      (node (ref "LED3_16") (pin "2") (pinfunction "2_2") (pintype "passive"))
      (node (ref "LED3_2") (pin "2") (pinfunction "2_2") (pintype "passive"))
      (node (ref "LED3_3") (pin "2") (pinfunction "2_2") (pintype "passive"))
      (node (ref "LED3_4") (pin "2") (pinfunction "2_2") (pintype "passive"))
      (node (ref "LED3_5") (pin "2") (pinfunction "2_2") (pintype "passive"))
      (node (ref "LED3_6") (pin "2") (pinfunction "2_2") (pintype "passive"))
      (node (ref "LED3_7") (pin "2") (pinfunction "2_2") (pintype "passive"))
      (node (ref "LED3_8") (pin "2") (pinfunction "2_2") (pintype "passive"))
      (node (ref "LED3_9") (pin "2") (pinfunction "2_2") (pintype "passive"))
      (node (ref "U2") (pin "4") (pinfunction "COM2KS1_4") (pintype "passive"))
    )
    (net (code "7") (name "Net-(U2-COM3KS2)") (class "Default")
      (node (ref "LED4_1") (pin "2") (pinfunction "2_2") (pintype "passive"))
      (node (ref "LED4_10") (pin "2") (pinfunction "2_2") (pintype "passive"))
      (node (ref "LED4_11") (pin "2") (pinfunction "2_2") (pintype "passive"))
      (node (ref "LED4_12") (pin "2") (pinfunction "2_2") (pintype "passive"))
      (node (ref "LED4_13") (pin "2") (pinfunction "2_2") (pintype "passive"))
      (node (ref "LED4_14") (pin "2") (pinfunction "2_2") (pintype "passive"))
      (node (ref "LED4_15") (pin "2") (pinfunction "2_2") (pintype "passive"))
      (node (ref "LED4_16") (pin "2") (pinfunction "2_2") (pintype "passive"))
      (node (ref "LED4_2") (pin "2") (pinfunction "2_2") (pintype "passive"))
      (node (ref "LED4_3") (pin "2") (pinfunction "2_2") (pintype "passive"))
      (node (ref "LED4_4") (pin "2") (pinfunction "2_2") (pintype "passive"))
      (node (ref "LED4_5") (pin "2") (pinfunction "2_2") (pintype "passive"))
      (node (ref "LED4_6") (pin "2") (pinfunction "2_2") (pintype "passive"))
      (node (ref "LED4_7") (pin "2") (pinfunction "2_2") (pintype "passive"))
      (node (ref "LED4_8") (pin "2") (pinfunction "2_2") (pintype "passive"))
      (node (ref "LED4_9") (pin "2") (pinfunction "2_2") (pintype "passive"))
      (node (ref "U2") (pin "5") (pinfunction "COM3KS2_5") (pintype "passive"))
    )
    (net (code "8") (name "Net-(U2-COM4)") (class "Default")
      (node (ref "LED5_1") (pin "2") (pinfunction "2_2") (pintype "passive"))
      (node (ref "LED5_10") (pin "2") (pinfunction "2_2") (pintype "passive"))
      (node (ref "LED5_11") (pin "2") (pinfunction "2_2") (pintype "passive"))
      (node (ref "LED5_12") (pin "2") (pinfunction "2_2") (pintype "passive"))
      (node (ref "LED5_13") (pin "2") (pinfunction "2_2") (pintype "passive"))
      (node (ref "LED5_14") (pin "2") (pinfunction "2_2") (pintype "passive"))
      (node (ref "LED5_15") (pin "2") (pinfunction "2_2") (pintype "passive"))
      (node (ref "LED5_16") (pin "2") (pinfunction "2_2") (pintype "passive"))
      (node (ref "LED5_2") (pin "2") (pinfunction "2_2") (pintype "passive"))
      (node (ref "LED5_3") (pin "2") (pinfunction "2_2") (pintype "passive"))
      (node (ref "LED5_4") (pin "2") (pinfunction "2_2") (pintype "passive"))
      (node (ref "LED5_5") (pin "2") (pinfunction "2_2") (pintype "passive"))
      (node (ref "LED5_6") (pin "2") (pinfunction "2_2") (pintype "passive"))
      (node (ref "LED5_7") (pin "2") (pinfunction "2_2") (pintype "passive"))
      (node (ref "LED5_8") (pin "2") (pinfunction "2_2") (pintype "passive"))
      (node (ref "LED5_9") (pin "2") (pinfunction "2_2") (pintype "passive"))
      (node (ref "U2") (pin "6") (pinfunction "COM4_6") (pintype "passive"))
    )
    (net (code "9") (name "Net-(U2-COM5)") (class "Default")
      (node (ref "LED6_1") (pin "2") (pinfunction "2_2") (pintype "passive"))
      (node (ref "LED6_10") (pin "2") (pinfunction "2_2") (pintype "passive"))
      (node (ref "LED6_11") (pin "2") (pinfunction "2_2") (pintype "passive"))
      (node (ref "LED6_12") (pin "2") (pinfunction "2_2") (pintype "passive"))
      (node (ref "LED6_13") (pin "2") (pinfunction "2_2") (pintype "passive"))
      (node (ref "LED6_14") (pin "2") (pinfunction "2_2") (pintype "passive"))
      (node (ref "LED6_15") (pin "2") (pinfunction "2_2") (pintype "passive"))
      (node (ref "LED6_16") (pin "2") (pinfunction "2_2") (pintype "passive"))
      (node (ref "LED6_2") (pin "2") (pinfunction "2_2") (pintype "passive"))
      (node (ref "LED6_3") (pin "2") (pinfunction "2_2") (pintype "passive"))
      (node (ref "LED6_4") (pin "2") (pinfunction "2_2") (pintype "passive"))
      (node (ref "LED6_5") (pin "2") (pinfunction "2_2") (pintype "passive"))
      (node (ref "LED6_6") (pin "2") (pinfunction "2_2") (pintype "passive"))
      (node (ref "LED6_7") (pin "2") (pinfunction "2_2") (pintype "passive"))
      (node (ref "LED6_8") (pin "2") (pinfunction "2_2") (pintype "passive"))
      (node (ref "LED6_9") (pin "2") (pinfunction "2_2") (pintype "passive"))
      (node (ref "U2") (pin "7") (pinfunction "COM5_7") (pintype "passive"))
    )
    (net (code "10") (name "Net-(U2-COM6)") (class "Default")
      (node (ref "LED7_1") (pin "2") (pinfunction "2_2") (pintype "passive"))
      (node (ref "LED7_10") (pin "2") (pinfunction "2_2") (pintype "passive"))
      (node (ref "LED7_11") (pin "2") (pinfunction "2_2") (pintype "passive"))
      (node (ref "LED7_12") (pin "2") (pinfunction "2_2") (pintype "passive"))
      (node (ref "LED7_13") (pin "2") (pinfunction "2_2") (pintype "passive"))
      (node (ref "LED7_14") (pin "2") (pinfunction "2_2") (pintype "passive"))
      (node (ref "LED7_15") (pin "2") (pinfunction "2_2") (pintype "passive"))
      (node (ref "LED7_16") (pin "2") (pinfunction "2_2") (pintype "passive"))
      (node (ref "LED7_2") (pin "2") (pinfunction "2_2") (pintype "passive"))
      (node (ref "LED7_3") (pin "2") (pinfunction "2_2") (pintype "passive"))
      (node (ref "LED7_4") (pin "2") (pinfunction "2_2") (pintype "passive"))
      (node (ref "LED7_5") (pin "2") (pinfunction "2_2") (pintype "passive"))
      (node (ref "LED7_6") (pin "2") (pinfunction "2_2") (pintype "passive"))
      (node (ref "LED7_7") (pin "2") (pinfunction "2_2") (pintype "passive"))
      (node (ref "LED7_8") (pin "2") (pinfunction "2_2") (pintype "passive"))
      (node (ref "LED7_9") (pin "2") (pinfunction "2_2") (pintype "passive"))
      (node (ref "U2") (pin "8") (pinfunction "COM6_8") (pintype "passive"))
    )
    (net (code "11") (name "Net-(U2-COM7)") (class "Default")
      (node (ref "LED8_1") (pin "2") (pinfunction "2_2") (pintype "passive"))
      (node (ref "LED8_10") (pin "2") (pinfunction "2_2") (pintype "passive"))
      (node (ref "LED8_11") (pin "2") (pinfunction "2_2") (pintype "passive"))
      (node (ref "LED8_12") (pin "2") (pinfunction "2_2") (pintype "passive"))
      (node (ref "LED8_13") (pin "2") (pinfunction "2_2") (pintype "passive"))
      (node (ref "LED8_14") (pin "2") (pinfunction "2_2") (pintype "passive"))
      (node (ref "LED8_15") (pin "2") (pinfunction "2_2") (pintype "passive"))
      (node (ref "LED8_16") (pin "2") (pinfunction "2_2") (pintype "passive"))
      (node (ref "LED8_2") (pin "2") (pinfunction "2_2") (pintype "passive"))
      (node (ref "LED8_3") (pin "2") (pinfunction "2_2") (pintype "passive"))
      (node (ref "LED8_4") (pin "2") (pinfunction "2_2") (pintype "passive"))
      (node (ref "LED8_5") (pin "2") (pinfunction "2_2") (pintype "passive"))
      (node (ref "LED8_6") (pin "2") (pinfunction "2_2") (pintype "passive"))
      (node (ref "LED8_7") (pin "2") (pinfunction "2_2") (pintype "passive"))
      (node (ref "LED8_8") (pin "2") (pinfunction "2_2") (pintype "passive"))
      (node (ref "LED8_9") (pin "2") (pinfunction "2_2") (pintype "passive"))
      (node (ref "U2") (pin "9") (pinfunction "COM7_9") (pintype "passive"))
    )
    (net (code "12") (name "Net-(U2-ROW0A2)") (class "Default")
      (node (ref "LED1_16") (pin "1") (pinfunction "1_1") (pintype "passive"))
      (node (ref "LED2_16") (pin "1") (pinfunction "1_1") (pintype "passive"))
      (node (ref "LED3_16") (pin "1") (pinfunction "1_1") (pintype "passive"))
      (node (ref "LED4_16") (pin "1") (pinfunction "1_1") (pintype "passive"))
      (node (ref "LED5_16") (pin "1") (pinfunction "1_1") (pintype "passive"))
      (node (ref "LED6_16") (pin "1") (pinfunction "1_1") (pintype "passive"))
      (node (ref "LED7_16") (pin "1") (pinfunction "1_1") (pintype "passive"))
      (node (ref "LED8_16") (pin "1") (pinfunction "1_1") (pintype "passive"))
      (node (ref "U2") (pin "25") (pinfunction "ROW0A2_25") (pintype "passive"))
    )
    (net (code "13") (name "Net-(U2-ROW1A1)") (class "Default")
      (node (ref "LED1_15") (pin "1") (pinfunction "1_1") (pintype "passive"))
      (node (ref "LED2_15") (pin "1") (pinfunction "1_1") (pintype "passive"))
      (node (ref "LED3_15") (pin "1") (pinfunction "1_1") (pintype "passive"))
      (node (ref "LED4_15") (pin "1") (pinfunction "1_1") (pintype "passive"))
      (node (ref "LED5_15") (pin "1") (pinfunction "1_1") (pintype "passive"))
      (node (ref "LED6_15") (pin "1") (pinfunction "1_1") (pintype "passive"))
      (node (ref "LED7_15") (pin "1") (pinfunction "1_1") (pintype "passive"))
      (node (ref "LED8_15") (pin "1") (pinfunction "1_1") (pintype "passive"))
      (node (ref "U2") (pin "24") (pinfunction "ROW1A1_24") (pintype "passive"))
    )
    (net (code "14") (name "Net-(U2-ROW2A0)") (class "Default")
      (node (ref "LED1_14") (pin "1") (pinfunction "1_1") (pintype "passive"))
      (node (ref "LED2_14") (pin "1") (pinfunction "1_1") (pintype "passive"))
      (node (ref "LED3_14") (pin "1") (pinfunction "1_1") (pintype "passive"))
      (node (ref "LED4_14") (pin "1") (pinfunction "1_1") (pintype "passive"))
      (node (ref "LED5_14") (pin "1") (pinfunction "1_1") (pintype "passive"))
      (node (ref "LED6_14") (pin "1") (pinfunction "1_1") (pintype "passive"))
      (node (ref "LED7_14") (pin "1") (pinfunction "1_1") (pintype "passive"))
      (node (ref "LED8_14") (pin "1") (pinfunction "1_1") (pintype "passive"))
      (node (ref "U2") (pin "23") (pinfunction "ROW2A0_23") (pintype "passive"))
    )
    (net (code "15") (name "Net-(U2-ROW3K1)") (class "Default")
      (node (ref "LED1_13") (pin "1") (pinfunction "1_1") (pintype "passive"))
      (node (ref "LED2_13") (pin "1") (pinfunction "1_1") (pintype "passive"))
      (node (ref "LED3_13") (pin "1") (pinfunction "1_1") (pintype "passive"))
      (node (ref "LED4_13") (pin "1") (pinfunction "1_1") (pintype "passive"))
      (node (ref "LED5_13") (pin "1") (pinfunction "1_1") (pintype "passive"))
      (node (ref "LED6_13") (pin "1") (pinfunction "1_1") (pintype "passive"))
      (node (ref "LED7_13") (pin "1") (pinfunction "1_1") (pintype "passive"))
      (node (ref "LED8_13") (pin "1") (pinfunction "1_1") (pintype "passive"))
      (node (ref "U2") (pin "22") (pinfunction "ROW3K1_22") (pintype "passive"))
    )
    (net (code "16") (name "Net-(U2-ROW4K2)") (class "Default")
      (node (ref "LED1_12") (pin "1") (pinfunction "1_1") (pintype "passive"))
      (node (ref "LED2_12") (pin "1") (pinfunction "1_1") (pintype "passive"))
      (node (ref "LED3_12") (pin "1") (pinfunction "1_1") (pintype "passive"))
      (node (ref "LED4_12") (pin "1") (pinfunction "1_1") (pintype "passive"))
      (node (ref "LED5_12") (pin "1") (pinfunction "1_1") (pintype "passive"))
      (node (ref "LED6_12") (pin "1") (pinfunction "1_1") (pintype "passive"))
      (node (ref "LED7_12") (pin "1") (pinfunction "1_1") (pintype "passive"))
      (node (ref "LED8_12") (pin "1") (pinfunction "1_1") (pintype "passive"))
      (node (ref "U2") (pin "21") (pinfunction "ROW4K2_21") (pintype "passive"))
    )
    (net (code "17") (name "Net-(U2-ROW5K3)") (class "Default")
      (node (ref "LED1_11") (pin "1") (pinfunction "1_1") (pintype "passive"))
      (node (ref "LED2_11") (pin "1") (pinfunction "1_1") (pintype "passive"))
      (node (ref "LED3_11") (pin "1") (pinfunction "1_1") (pintype "passive"))
      (node (ref "LED4_11") (pin "1") (pinfunction "1_1") (pintype "passive"))
      (node (ref "LED5_11") (pin "1") (pinfunction "1_1") (pintype "passive"))
      (node (ref "LED6_11") (pin "1") (pinfunction "1_1") (pintype "passive"))
      (node (ref "LED7_11") (pin "1") (pinfunction "1_1") (pintype "passive"))
      (node (ref "LED8_11") (pin "1") (pinfunction "1_1") (pintype "passive"))
      (node (ref "U2") (pin "20") (pinfunction "ROW5K3_20") (pintype "passive"))
    )
    (net (code "18") (name "Net-(U2-ROW6K4)") (class "Default")
      (node (ref "LED1_10") (pin "1") (pinfunction "1_1") (pintype "passive"))
      (node (ref "LED2_10") (pin "1") (pinfunction "1_1") (pintype "passive"))
      (node (ref "LED3_10") (pin "1") (pinfunction "1_1") (pintype "passive"))
      (node (ref "LED4_10") (pin "1") (pinfunction "1_1") (pintype "passive"))
      (node (ref "LED5_10") (pin "1") (pinfunction "1_1") (pintype "passive"))
      (node (ref "LED6_10") (pin "1") (pinfunction "1_1") (pintype "passive"))
      (node (ref "LED7_10") (pin "1") (pinfunction "1_1") (pintype "passive"))
      (node (ref "LED8_10") (pin "1") (pinfunction "1_1") (pintype "passive"))
      (node (ref "U2") (pin "19") (pinfunction "ROW6K4_19") (pintype "passive"))
    )
    (net (code "19") (name "Net-(U2-ROW7K5)") (class "Default")
      (node (ref "LED1_9") (pin "1") (pinfunction "1_1") (pintype "passive"))
      (node (ref "LED2_9") (pin "1") (pinfunction "1_1") (pintype "passive"))
      (node (ref "LED3_9") (pin "1") (pinfunction "1_1") (pintype "passive"))
      (node (ref "LED4_9") (pin "1") (pinfunction "1_1") (pintype "passive"))
      (node (ref "LED5_9") (pin "1") (pinfunction "1_1") (pintype "passive"))
      (node (ref "LED6_9") (pin "1") (pinfunction "1_1") (pintype "passive"))
      (node (ref "LED7_9") (pin "1") (pinfunction "1_1") (pintype "passive"))
      (node (ref "LED8_9") (pin "1") (pinfunction "1_1") (pintype "passive"))
      (node (ref "U2") (pin "18") (pinfunction "ROW7K5_18") (pintype "passive"))
    )
    (net (code "20") (name "Net-(U2-ROW8K6)") (class "Default")
      (node (ref "LED1_8") (pin "1") (pinfunction "1_1") (pintype "passive"))
      (node (ref "LED2_8") (pin "1") (pinfunction "1_1") (pintype "passive"))
      (node (ref "LED3_8") (pin "1") (pinfunction "1_1") (pintype "passive"))
      (node (ref "LED4_8") (pin "1") (pinfunction "1_1") (pintype "passive"))
      (node (ref "LED5_8") (pin "1") (pinfunction "1_1") (pintype "passive"))
      (node (ref "LED6_8") (pin "1") (pinfunction "1_1") (pintype "passive"))
      (node (ref "LED7_8") (pin "1") (pinfunction "1_1") (pintype "passive"))
      (node (ref "LED8_8") (pin "1") (pinfunction "1_1") (pintype "passive"))
      (node (ref "U2") (pin "17") (pinfunction "ROW8K6_17") (pintype "passive"))
    )
    (net (code "21") (name "Net-(U2-ROW9K7)") (class "Default")
      (node (ref "LED1_7") (pin "1") (pinfunction "1_1") (pintype "passive"))
      (node (ref "LED2_7") (pin "1") (pinfunction "1_1") (pintype "passive"))
      (node (ref "LED3_7") (pin "1") (pinfunction "1_1") (pintype "passive"))
      (node (ref "LED4_7") (pin "1") (pinfunction "1_1") (pintype "passive"))
      (node (ref "LED5_7") (pin "1") (pinfunction "1_1") (pintype "passive"))
      (node (ref "LED6_7") (pin "1") (pinfunction "1_1") (pintype "passive"))
      (node (ref "LED7_7") (pin "1") (pinfunction "1_1") (pintype "passive"))
      (node (ref "LED8_7") (pin "1") (pinfunction "1_1") (pintype "passive"))
      (node (ref "U2") (pin "16") (pinfunction "ROW9K7_16") (pintype "passive"))
    )
    (net (code "22") (name "Net-(U2-ROW10K8)") (class "Default")
      (node (ref "LED1_6") (pin "1") (pinfunction "1_1") (pintype "passive"))
      (node (ref "LED2_6") (pin "1") (pinfunction "1_1") (pintype "passive"))
      (node (ref "LED3_6") (pin "1") (pinfunction "1_1") (pintype "passive"))
      (node (ref "LED4_6") (pin "1") (pinfunction "1_1") (pintype "passive"))
      (node (ref "LED5_6") (pin "1") (pinfunction "1_1") (pintype "passive"))
      (node (ref "LED6_6") (pin "1") (pinfunction "1_1") (pintype "passive"))
      (node (ref "LED7_6") (pin "1") (pinfunction "1_1") (pintype "passive"))
      (node (ref "LED8_6") (pin "1") (pinfunction "1_1") (pintype "passive"))
      (node (ref "U2") (pin "15") (pinfunction "ROW10K8_15") (pintype "passive"))
    )
    (net (code "23") (name "Net-(U2-ROW11K9)") (class "Default")
      (node (ref "LED1_5") (pin "1") (pinfunction "1_1") (pintype "passive"))
      (node (ref "LED2_5") (pin "1") (pinfunction "1_1") (pintype "passive"))
      (node (ref "LED3_5") (pin "1") (pinfunction "1_1") (pintype "passive"))
      (node (ref "LED4_5") (pin "1") (pinfunction "1_1") (pintype "passive"))
      (node (ref "LED5_5") (pin "1") (pinfunction "1_1") (pintype "passive"))
      (node (ref "LED6_5") (pin "1") (pinfunction "1_1") (pintype "passive"))
      (node (ref "LED7_5") (pin "1") (pinfunction "1_1") (pintype "passive"))
      (node (ref "LED8_5") (pin "1") (pinfunction "1_1") (pintype "passive"))
      (node (ref "U2") (pin "14") (pinfunction "ROW11K9_14") (pintype "passive"))
    )
    (net (code "24") (name "Net-(U2-ROW12K10)") (class "Default")
      (node (ref "LED1_4") (pin "1") (pinfunction "1_1") (pintype "passive"))
      (node (ref "LED2_4") (pin "1") (pinfunction "1_1") (pintype "passive"))
      (node (ref "LED3_4") (pin "1") (pinfunction "1_1") (pintype "passive"))
      (node (ref "LED4_4") (pin "1") (pinfunction "1_1") (pintype "passive"))
      (node (ref "LED5_4") (pin "1") (pinfunction "1_1") (pintype "passive"))
      (node (ref "LED6_4") (pin "1") (pinfunction "1_1") (pintype "passive"))
      (node (ref "LED7_4") (pin "1") (pinfunction "1_1") (pintype "passive"))
      (node (ref "LED8_4") (pin "1") (pinfunction "1_1") (pintype "passive"))
      (node (ref "U2") (pin "13") (pinfunction "ROW12K10_13") (pintype "passive"))
    )
    (net (code "25") (name "Net-(U2-ROW13K11)") (class "Default")
      (node (ref "LED1_3") (pin "1") (pinfunction "1_1") (pintype "passive"))
      (node (ref "LED2_3") (pin "1") (pinfunction "1_1") (pintype "passive"))
      (node (ref "LED3_3") (pin "1") (pinfunction "1_1") (pintype "passive"))
      (node (ref "LED4_3") (pin "1") (pinfunction "1_1") (pintype "passive"))
      (node (ref "LED5_3") (pin "1") (pinfunction "1_1") (pintype "passive"))
      (node (ref "LED6_3") (pin "1") (pinfunction "1_1") (pintype "passive"))
      (node (ref "LED7_3") (pin "1") (pinfunction "1_1") (pintype "passive"))
      (node (ref "LED8_3") (pin "1") (pinfunction "1_1") (pintype "passive"))
      (node (ref "U2") (pin "12") (pinfunction "ROW13K11_12") (pintype "passive"))
    )
    (net (code "26") (name "Net-(U2-ROW14K12)") (class "Default")
      (node (ref "LED1_2") (pin "1") (pinfunction "1_1") (pintype "passive"))
      (node (ref "LED2_2") (pin "1") (pinfunction "1_1") (pintype "passive"))
      (node (ref "LED3_2") (pin "1") (pinfunction "1_1") (pintype "passive"))
      (node (ref "LED4_2") (pin "1") (pinfunction "1_1") (pintype "passive"))
      (node (ref "LED5_2") (pin "1") (pinfunction "1_1") (pintype "passive"))
      (node (ref "LED6_2") (pin "1") (pinfunction "1_1") (pintype "passive"))
      (node (ref "LED7_2") (pin "1") (pinfunction "1_1") (pintype "passive"))
      (node (ref "LED8_2") (pin "1") (pinfunction "1_1") (pintype "passive"))
      (node (ref "U2") (pin "11") (pinfunction "ROW14K12_11") (pintype "passive"))
    )
    (net (code "27") (name "Net-(U2-ROW15K13INT)") (class "Default")
      (node (ref "LED1_1") (pin "1") (pinfunction "1_1") (pintype "passive"))
      (node (ref "LED2_1") (pin "1") (pinfunction "1_1") (pintype "passive"))
      (node (ref "LED3_1") (pin "1") (pinfunction "1_1") (pintype "passive"))
      (node (ref "LED4_1") (pin "1") (pinfunction "1_1") (pintype "passive"))
      (node (ref "LED5_1") (pin "1") (pinfunction "1_1") (pintype "passive"))
      (node (ref "LED6_1") (pin "1") (pinfunction "1_1") (pintype "passive"))
      (node (ref "LED7_1") (pin "1") (pinfunction "1_1") (pintype "passive"))
      (node (ref "LED8_1") (pin "1") (pinfunction "1_1") (pintype "passive"))
      (node (ref "U2") (pin "10") (pinfunction "ROW15K13INT_10") (pintype "passive"))
    )
    (net (code "28") (name "Net-(U2-SCL)") (class "Default")
      (node (ref "R2") (pin "1") (pinfunction "1_1") (pintype "passive"))
      (node (ref "U2") (pin "26") (pinfunction "SCL_26") (pintype "passive"))
    )
    (net (code "29") (name "Net-(U2-SDA)") (class "Default")
      (node (ref "R1") (pin "1") (pinfunction "1_1") (pintype "passive"))
      (node (ref "U2") (pin "27") (pinfunction "SDA_27") (pintype "passive"))
    )
    (net (code "30") (name "VCC") (class "Default")
      (node (ref "U1") (pin "8") (pinfunction "VCC_8") (pintype "passive"))
      (node (ref "U2") (pin "28") (pinfunction "VCC_28") (pintype "passive"))
    )
    (net (code "31") (name "unconnected-(U1-PB1_(MISO{slash}DO{slash}AIN1{slash}OC0B{slash}OC1A{slash}PCINT1)-Pad6)") (class "Default")
      (node (ref "U1") (pin "6") (pinfunction "PB1_(MISO/DO/AIN1/OC0B/OC1A/PCINT1)_6") (pintype "passive+no_connect"))
    )
    (net (code "32") (name "unconnected-(U1-PB3_(PCINT3{slash}XTAL1{slash}CLKI{slash}OC1B{slash}ADC3)-Pad2)") (class "Default")
      (node (ref "U1") (pin "2") (pinfunction "PB3_(PCINT3/XTAL1/CLKI/OC1B/ADC3)_2") (pintype "passive+no_connect"))
    )
    (net (code "33") (name "unconnected-(U1-PB4_(PCINT4{slash}XTAL2{slash}CLKO{slash}OC1B{slash}ADC2)-Pad3)") (class "Default")
      (node (ref "U1") (pin "3") (pinfunction "PB4_(PCINT4/XTAL2/CLKO/OC1B/ADC2)_3") (pintype "passive+no_connect"))
    )
    (net (code "34") (name "unconnected-(U1-PB5_(PCINT5{slash}RESET{slash}ADC0{slash}DW)-Pad1)") (class "Default")
      (node (ref "U1") (pin "1") (pinfunction "PB5_(PCINT5/RESET/ADC0/DW)_1") (pintype "passive+no_connect"))
    )
  )
)
